# 3V8_SWITCHER.net
KiCad netlist of a schematic drawn in Altium Designer
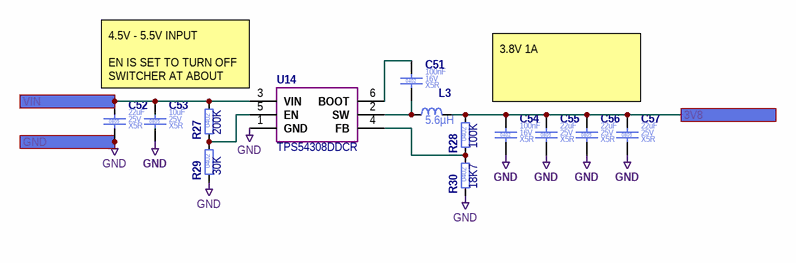
[diagram p0: 3V8_SWITCHER.SchDoc]

(export (version "E")
  (design (tool "Eeschema 10.0.6"))
  (components
    (comp (ref "C51")
      (value "C_100NF_16V_X5R_0402_10")
      (footprint "C_0402_1005")
      (description "Ceramic Capacitor")
      (fields
        (field (name "CASE/PACKAGE") "0402")
        (field (name "VOLTAGE RATING (DC)") "16V")
        (field (name "DIELECTRIC") "X5R")
        (field (name "CAPACITANCE") "100nF")
        (field (name "TOLERANCE") "10%")
        (field (name "MANUFACTURER PART NUMBER") "EMK105BJ104KV-F")
      )
      (libsource (lib "7Sigma") (part "C"))
    )
    (comp (ref "C52")
      (value "C_22UF_25V_X5R_0805_20")
      (footprint "C_0805_2012")
      (description "Ceramic Capacitor")
      (fields
        (field (name "CASE/PACKAGE") "0805")
        (field (name "VOLTAGE RATING (DC)") "25V")
        (field (name "DIELECTRIC") "X5R")
        (field (name "CAPACITANCE") "22uF")
        (field (name "TOLERANCE") "20%")
        (field (name "MANUFACTURER PART NUMBER") "GRM21BR61E226ME44K")
      )
      (libsource (lib "7Sigma") (part "C"))
    )
    (comp (ref "C53")
      (value "C_10UF_25V_X5R_0805_10")
      (footprint "C_0805_2012")
      (description "Ceramic Capacitor")
      (fields
        (field (name "CASE/PACKAGE") "0805")
        (field (name "VOLTAGE RATING (DC)") "25V")
        (field (name "DIELECTRIC") "X5R")
        (field (name "CAPACITANCE") "10uF")
        (field (name "TOLERANCE") "10%")
        (field (name "MANUFACTURER PART NUMBER") "CL21A106KAYNNNE")
      )
      (libsource (lib "7Sigma") (part "C"))
    )
    (comp (ref "C54")
      (value "C_100NF_16V_X5R_0402_10")
      (footprint "C_0402_1005")
      (description "Ceramic Capacitor")
      (fields
        (field (name "CASE/PACKAGE") "0402")
        (field (name "VOLTAGE RATING (DC)") "16V")
        (field (name "DIELECTRIC") "X5R")
        (field (name "CAPACITANCE") "100nF")
        (field (name "TOLERANCE") "10%")
        (field (name "MANUFACTURER PART NUMBER") "EMK105BJ104KV-F")
      )
      (libsource (lib "7Sigma") (part "C"))
    )
    (comp (ref "C55")
      (value "C_22UF_25V_X5R_0805_20")
      (footprint "C_0805_2012")
      (description "Ceramic Capacitor")
      (fields
        (field (name "CASE/PACKAGE") "0805")
        (field (name "VOLTAGE RATING (DC)") "25V")
        (field (name "DIELECTRIC") "X5R")
        (field (name "CAPACITANCE") "22uF")
        (field (name "TOLERANCE") "20%")
        (field (name "MANUFACTURER PART NUMBER") "GRM21BR61E226ME44K")
      )
      (libsource (lib "7Sigma") (part "C"))
    )
    (comp (ref "C56")
      (value "C_22UF_25V_X5R_0805_20")
      (footprint "C_0805_2012")
      (description "Ceramic Capacitor")
      (fields
        (field (name "CASE/PACKAGE") "0805")
        (field (name "VOLTAGE RATING (DC)") "25V")
        (field (name "DIELECTRIC") "X5R")
        (field (name "CAPACITANCE") "22uF")
        (field (name "TOLERANCE") "20%")
        (field (name "MANUFACTURER PART NUMBER") "GRM21BR61E226ME44K")
      )
      (libsource (lib "7Sigma") (part "C"))
    )
    (comp (ref "C57")
      (value "C_22UF_25V_X5R_0805_20")
      (footprint "C_0805_2012")
      (description "Ceramic Capacitor")
      (fields
        (field (name "CASE/PACKAGE") "0805")
        (field (name "VOLTAGE RATING (DC)") "25V")
        (field (name "DIELECTRIC") "X5R")
        (field (name "CAPACITANCE") "22uF")
        (field (name "TOLERANCE") "20%")
        (field (name "MANUFACTURER PART NUMBER") "GRM21BR61E226ME44K")
      )
      (libsource (lib "7Sigma") (part "C"))
    )
    (comp (ref "L3")
      (value "74438357056")
      (footprint "WE-MAPI_4030")
      (description "Power Inductor")
      (fields
        (field (name "INDUCTANCE") "5.6µH")
        (field (name "MANUFACTURER") "Wurth Electronics")
        (field (name "TOLERANCE") "20%")
      )
      (libsource (lib "7Sigma") (part "L"))
    )
    (comp (ref "R27")
      (value "R_200K_0402_1")
      (footprint "R_0402_1005")
      (description "Thick Film Resistor")
      (fields
        (field (name "RESISTANCE") "200K")
        (field (name "CASE/PACKAGE") "0402")
        (field (name "TOLERANCE") "1%")
        (field (name "MANUFACTURER") "Yageo")
      )
      (libsource (lib "7Sigma") (part "R"))
    )
    (comp (ref "R28")
      (value "R_100K_0402_1")
      (footprint "R_0402_1005")
      (description "Thick Film Resistor")
      (fields
        (field (name "RESISTANCE") "100K")
        (field (name "CASE/PACKAGE") "0402")
        (field (name "TOLERANCE") "1%")
        (field (name "MANUFACTURER") "Yageo")
      )
      (libsource (lib "7Sigma") (part "R"))
    )
    (comp (ref "R29")
      (value "R_30K_0402_1")
      (footprint "R_0402_1005")
      (description "Thick Film Resistor")
      (fields
        (field (name "RESISTANCE") "30K")
        (field (name "CASE/PACKAGE") "0402")
        (field (name "TOLERANCE") "1%")
        (field (name "MANUFACTURER") "Yageo")
      )
      (libsource (lib "7Sigma") (part "R"))
    )
    (comp (ref "R30")
      (value "R_18K7_0402_1")
      (footprint "R_0402_1005")
      (description "Thick Film Resistor")
      (fields
        (field (name "RESISTANCE") "18K7")
        (field (name "CASE/PACKAGE") "0402")
        (field (name "TOLERANCE") "1%")
        (field (name "MANUFACTURER") "Yageo")
      )
      (libsource (lib "7Sigma") (part "R"))
    )
    (comp (ref "U14")
      (value "TPS54308DDCR")
      (footprint "SOT23-6_SC74A_SOT753")
      (description "FCCM SYNCHRONOUS STEP DOWN CONVE")
      (fields (field (name "MANUFACTURER") "Texas Instruments"))
      (libsource (lib "7Sigma") (part "TPS54308DDCR"))
    )
  )
  (nets
    (net (code "1") (name "/3V8") (class "Default")
      (node (ref "C54") (pin "1") (pinfunction "1_1") (pintype "passive"))
      (node (ref "C55") (pin "1") (pinfunction "1_1") (pintype "passive"))
      (node (ref "C56") (pin "1") (pinfunction "1_1") (pintype "passive"))
      (node (ref "C57") (pin "1") (pinfunction "1_1") (pintype "passive"))
      (node (ref "L3") (pin "2") (pinfunction "2_2") (pintype "passive"))
      (node (ref "R28") (pin "2") (pinfunction "2_2") (pintype "passive"))
    )
    (net (code "2") (name "/VIN") (class "Default")
      (node (ref "C52") (pin "1") (pinfunction "1_1") (pintype "passive"))
      (node (ref "C53") (pin "1") (pinfunction "1_1") (pintype "passive"))
      (node (ref "R27") (pin "2") (pinfunction "2_2") (pintype "passive"))
      (node (ref "U14") (pin "3") (pinfunction "VIN_3") (pintype "passive"))
    )
    (net (code "3") (name "GND") (class "Default")
      (node (ref "C52") (pin "2") (pinfunction "2_2") (pintype "passive"))
      (node (ref "C53") (pin "2") (pinfunction "2_2") (pintype "passive"))
      (node (ref "C54") (pin "2") (pinfunction "2_2") (pintype "passive"))
      (node (ref "C55") (pin "2") (pinfunction "2_2") (pintype "passive"))
      (node (ref "C56") (pin "2") (pinfunction "2_2") (pintype "passive"))
      (node (ref "C57") (pin "2") (pinfunction "2_2") (pintype "passive"))
      (node (ref "R29") (pin "1") (pinfunction "1_1") (pintype "passive"))
      (node (ref "R30") (pin "1") (pinfunction "1_1") (pintype "passive"))
      (node (ref "U14") (pin "1") (pinfunction "GND_1") (pintype "passive"))
    )
    (net (code "4") (name "Net-(U14-BOOT)") (class "Default")
      (node (ref "C51") (pin "1") (pinfunction "1_1") (pintype "passive"))
      (node (ref "U14") (pin "6") (pinfunction "BOOT_6") (pintype "passive"))
    )
    (net (code "5") (name "Net-(U14-EN)") (class "Default")
      (node (ref "R27") (pin "1") (pinfunction "1_1") (pintype "passive"))
      (node (ref "R29") (pin "2") (pinfunction "2_2") (pintype "passive"))
      (node (ref "U14") (pin "5") (pinfunction "EN_5") (pintype "passive"))
    )
    (net (code "6") (name "Net-(U14-FB)") (class "Default")
      (node (ref "R28") (pin "1") (pinfunction "1_1") (pintype "passive"))
      (node (ref "R30") (pin "2") (pinfunction "2_2") (pintype "passive"))
      (node (ref "U14") (pin "4") (pinfunction "FB_4") (pintype "passive"))
    )
    (net (code "7") (name "Net-(U14-SW)") (class "Default")
      (node (ref "C51") (pin "2") (pinfunction "2_2") (pintype "passive"))
      (node (ref "L3") (pin "1") (pinfunction "1_1") (pintype "passive"))
      (node (ref "U14") (pin "2") (pinfunction "SW_2") (pintype "passive"))
    )
  )
)
